# nola6.net
KiCad netlist of a schematic drawn in EAGLE
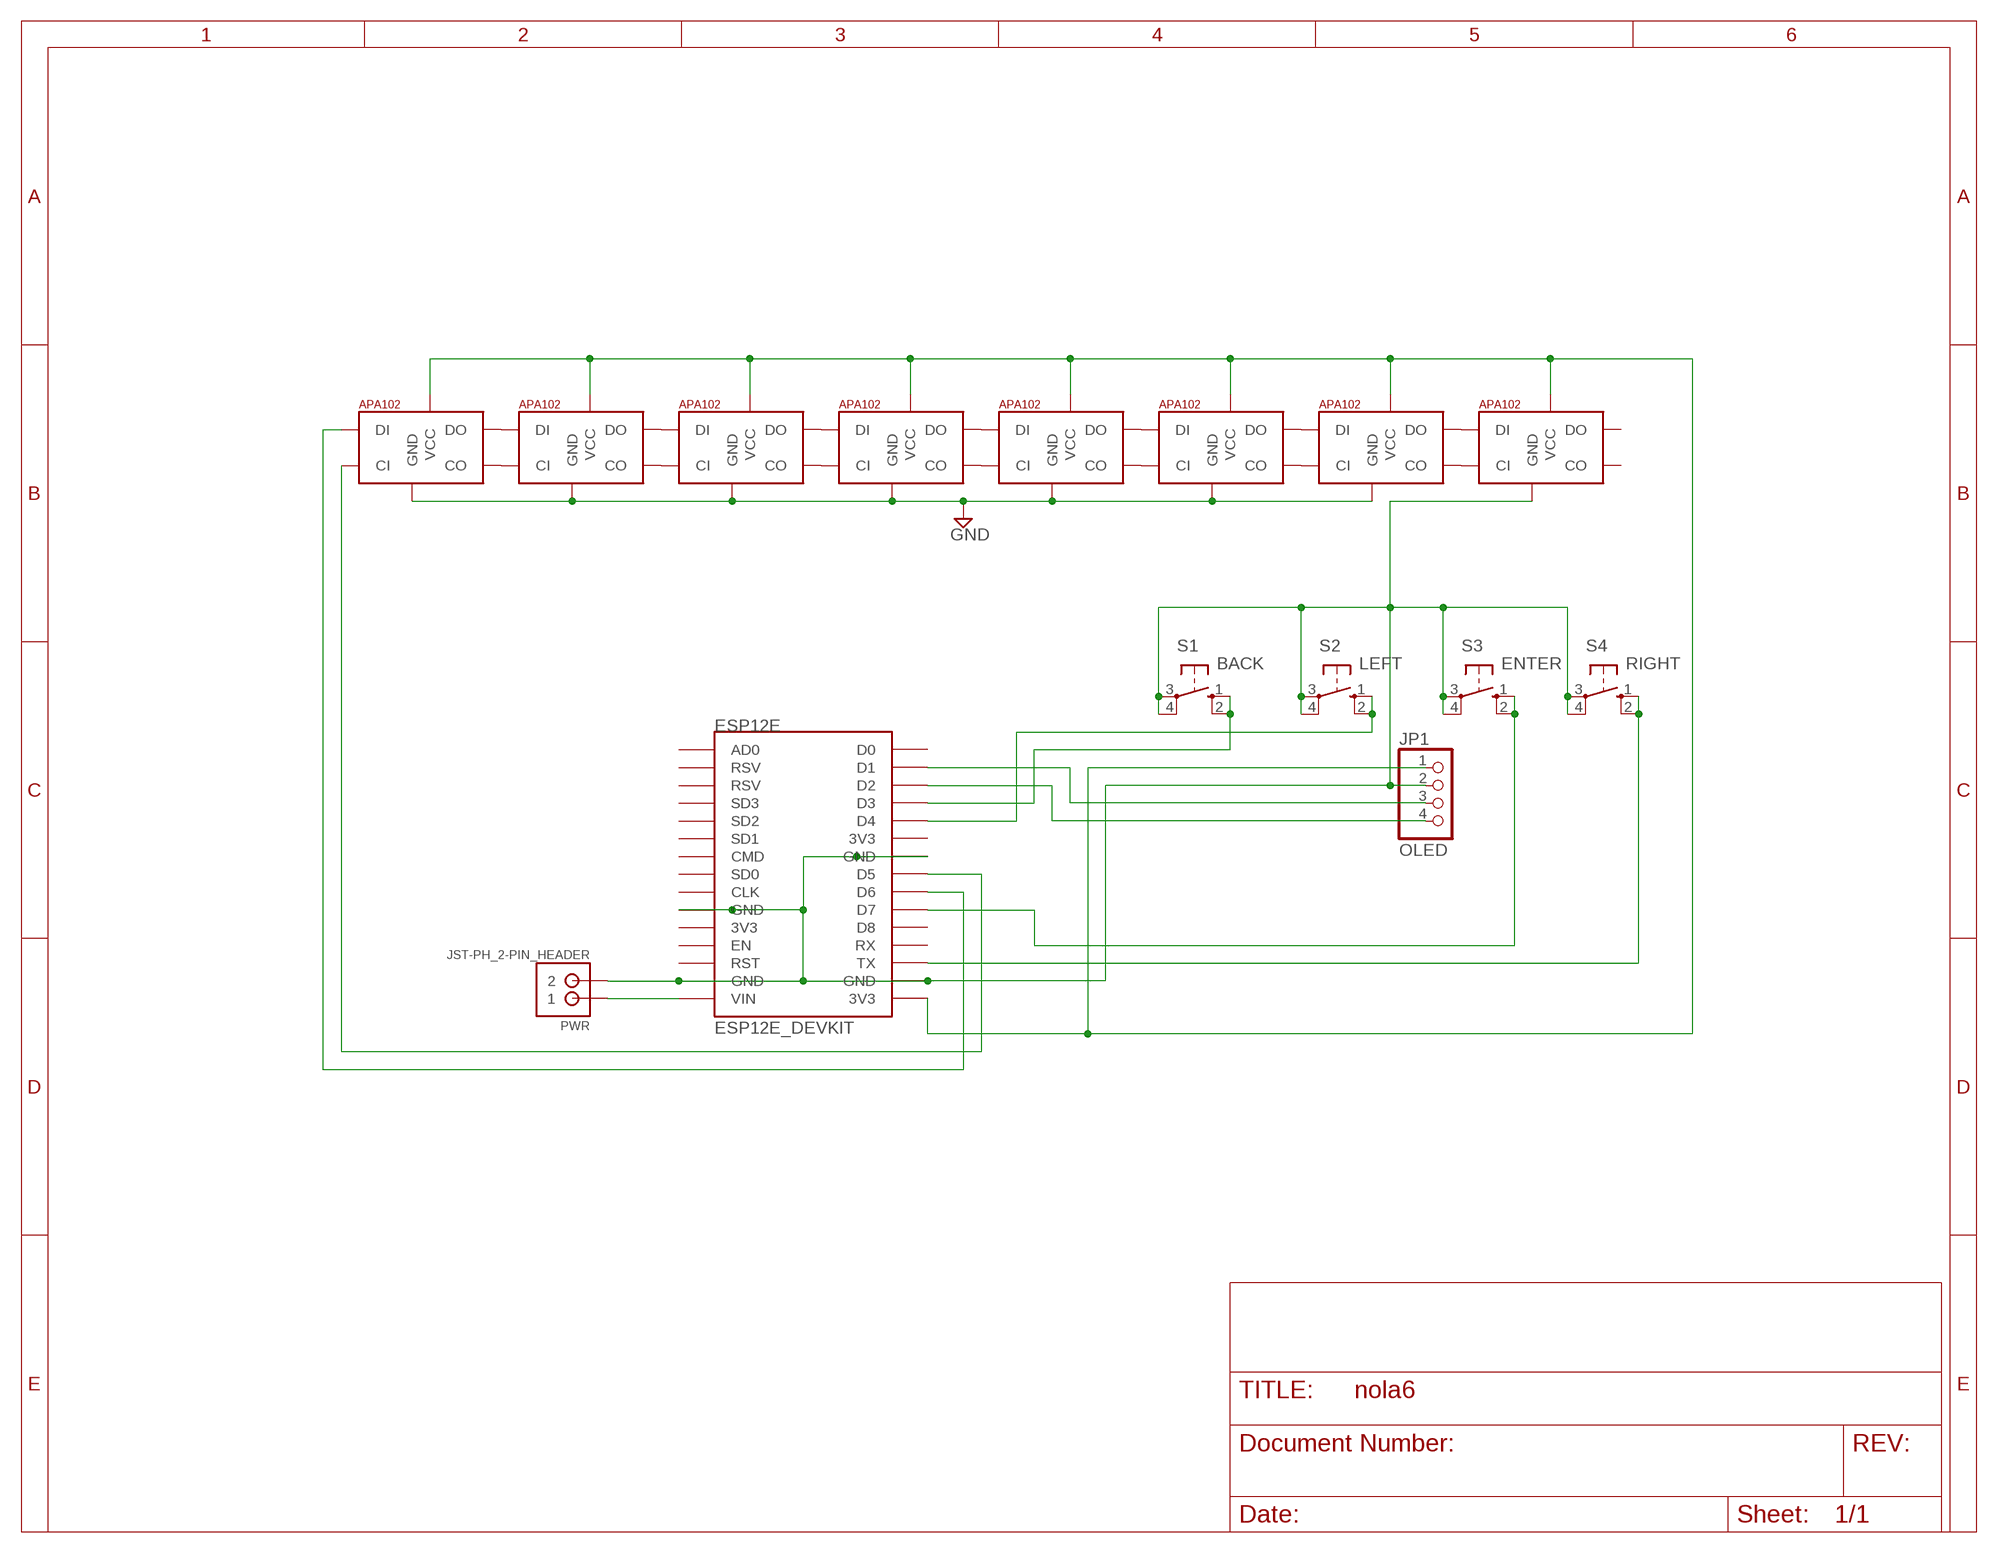
[diagram p0: schematic, sheet 1]

(export (version "E")
  (design (tool "Eeschema 10.0.6"))
  (components
    (comp (ref "ESP12E")
      (value "ESP12E_DEVKIT")
      (footprint "eagle-import:ESP12E_DEVKIT")
      (libsource (lib "eagle-import") (part "ESP12E_DEVKIT"))
    )
    (comp (ref "JP1")
      (value "OLED")
      (footprint "eagle-import:1X04")
      (libsource (lib "eagle-import") (part "PINHD-1X4"))
    )
    (comp (ref "LED1")
      (value "APA1025050")
      (footprint "eagle-import:APA102_5050")
      (libsource (lib "eagle-import") (part "APA1025050"))
    )
    (comp (ref "LED2")
      (value "APA1025050")
      (footprint "eagle-import:APA102_5050")
      (libsource (lib "eagle-import") (part "APA1025050"))
    )
    (comp (ref "LED3")
      (value "APA1025050")
      (footprint "eagle-import:APA102_5050")
      (libsource (lib "eagle-import") (part "APA1025050"))
    )
    (comp (ref "LED4")
      (value "APA1025050")
      (footprint "eagle-import:APA102_5050")
      (libsource (lib "eagle-import") (part "APA1025050"))
    )
    (comp (ref "LED5")
      (value "APA1025050")
      (footprint "eagle-import:APA102_5050")
      (libsource (lib "eagle-import") (part "APA1025050"))
    )
    (comp (ref "LED6")
      (value "APA1025050")
      (footprint "eagle-import:APA102_5050")
      (libsource (lib "eagle-import") (part "APA1025050"))
    )
    (comp (ref "LED7")
      (value "APA1025050")
      (footprint "eagle-import:APA102_5050")
      (libsource (lib "eagle-import") (part "APA1025050"))
    )
    (comp (ref "LED8")
      (value "APA1025050")
      (footprint "eagle-import:APA102_5050")
      (libsource (lib "eagle-import") (part "APA1025050"))
    )
    (comp (ref "PWR")
      (value "JST-PH_2-PIN_HEADER")
      (footprint "eagle-import:JST_B2B-PH_HEADER")
      (libsource (lib "eagle-import") (part "JST-PH_2-PIN_HEADER"))
    )
    (comp (ref "S1")
      (value "BACK")
      (footprint "eagle-import:B3F-10XX")
      (fields (field (name "MPN") "B3F-1000"))
      (libsource (lib "eagle-import") (part "10-XX"))
    )
    (comp (ref "S2")
      (value "LEFT")
      (footprint "eagle-import:B3F-10XX")
      (fields (field (name "MPN") "B3F-1000"))
      (libsource (lib "eagle-import") (part "10-XX"))
    )
    (comp (ref "S3")
      (value "ENTER")
      (footprint "eagle-import:B3F-10XX")
      (fields (field (name "MPN") "B3F-1000"))
      (libsource (lib "eagle-import") (part "10-XX"))
    )
    (comp (ref "S4")
      (value "RIGHT")
      (footprint "eagle-import:B3F-10XX")
      (fields (field (name "MPN") "B3F-1000"))
      (libsource (lib "eagle-import") (part "10-XX"))
    )
  )
  (nets
    (net (code "1") (name "GND") (class "Default")
      (node (ref "ESP12E") (pin "GND@0") (pinfunction "GND_GND@0") (pintype "bidirectional"))
      (node (ref "ESP12E") (pin "GND@1") (pinfunction "GND_GND@1") (pintype "bidirectional"))
      (node (ref "ESP12E") (pin "GND@2") (pinfunction "GND_GND@2") (pintype "bidirectional"))
      (node (ref "ESP12E") (pin "GND@3") (pinfunction "GND_GND@3") (pintype "bidirectional"))
      (node (ref "JP1") (pin "2") (pinfunction "2_2") (pintype "passive"))
      (node (ref "LED1") (pin "6") (pinfunction "GND_6") (pintype "bidirectional"))
      (node (ref "LED2") (pin "6") (pinfunction "GND_6") (pintype "bidirectional"))
      (node (ref "LED3") (pin "6") (pinfunction "GND_6") (pintype "bidirectional"))
      (node (ref "LED4") (pin "6") (pinfunction "GND_6") (pintype "bidirectional"))
      (node (ref "LED5") (pin "6") (pinfunction "GND_6") (pintype "bidirectional"))
      (node (ref "LED6") (pin "6") (pinfunction "GND_6") (pintype "bidirectional"))
      (node (ref "LED7") (pin "6") (pinfunction "GND_6") (pintype "bidirectional"))
      (node (ref "LED8") (pin "6") (pinfunction "GND_6") (pintype "bidirectional"))
      (node (ref "PWR") (pin "P2") (pinfunction "2_P2") (pintype "bidirectional"))
      (node (ref "S1") (pin "3") (pinfunction "P_3") (pintype "passive"))
      (node (ref "S1") (pin "4") (pinfunction "P1_4") (pintype "passive"))
      (node (ref "S2") (pin "3") (pinfunction "P_3") (pintype "passive"))
      (node (ref "S2") (pin "4") (pinfunction "P1_4") (pintype "passive"))
      (node (ref "S3") (pin "3") (pinfunction "P_3") (pintype "passive"))
      (node (ref "S3") (pin "4") (pinfunction "P1_4") (pintype "passive"))
      (node (ref "S4") (pin "3") (pinfunction "P_3") (pintype "passive"))
      (node (ref "S4") (pin "4") (pinfunction "P1_4") (pintype "passive"))
    )
    (net (code "2") (name "Net-(ESP12E-PadD1)") (class "Default")
      (node (ref "ESP12E") (pin "D1") (pinfunction "D1_D1") (pintype "bidirectional"))
      (node (ref "JP1") (pin "3") (pinfunction "3_3") (pintype "passive"))
    )
    (net (code "3") (name "Net-(ESP12E-PadD2)") (class "Default")
      (node (ref "ESP12E") (pin "D2") (pinfunction "D2_D2") (pintype "bidirectional"))
      (node (ref "JP1") (pin "4") (pinfunction "4_4") (pintype "passive"))
    )
    (net (code "4") (name "Net-(LED1-CI)") (class "Default")
      (node (ref "ESP12E") (pin "D5") (pinfunction "D5_D5") (pintype "bidirectional"))
      (node (ref "LED1") (pin "5") (pinfunction "CI_5") (pintype "bidirectional"))
    )
    (net (code "5") (name "Net-(LED1-CO)") (class "Default")
      (node (ref "LED1") (pin "2") (pinfunction "CO_2") (pintype "bidirectional"))
      (node (ref "LED2") (pin "5") (pinfunction "CI_5") (pintype "bidirectional"))
    )
    (net (code "6") (name "Net-(LED1-DI)") (class "Default")
      (node (ref "ESP12E") (pin "D6") (pinfunction "D6_D6") (pintype "bidirectional"))
      (node (ref "LED1") (pin "4") (pinfunction "DI_4") (pintype "bidirectional"))
    )
    (net (code "7") (name "Net-(LED1-DO)") (class "Default")
      (node (ref "LED1") (pin "3") (pinfunction "DO_3") (pintype "bidirectional"))
      (node (ref "LED2") (pin "4") (pinfunction "DI_4") (pintype "bidirectional"))
    )
    (net (code "8") (name "Net-(LED1-VCC)") (class "Default")
      (node (ref "ESP12E") (pin "3V3@2") (pinfunction "3V3_3V3@2") (pintype "bidirectional"))
      (node (ref "JP1") (pin "1") (pinfunction "1_1") (pintype "passive"))
      (node (ref "LED1") (pin "1") (pinfunction "VCC_1") (pintype "bidirectional"))
      (node (ref "LED2") (pin "1") (pinfunction "VCC_1") (pintype "bidirectional"))
      (node (ref "LED3") (pin "1") (pinfunction "VCC_1") (pintype "bidirectional"))
      (node (ref "LED4") (pin "1") (pinfunction "VCC_1") (pintype "bidirectional"))
      (node (ref "LED5") (pin "1") (pinfunction "VCC_1") (pintype "bidirectional"))
      (node (ref "LED6") (pin "1") (pinfunction "VCC_1") (pintype "bidirectional"))
      (node (ref "LED7") (pin "1") (pinfunction "VCC_1") (pintype "bidirectional"))
      (node (ref "LED8") (pin "1") (pinfunction "VCC_1") (pintype "bidirectional"))
    )
    (net (code "9") (name "Net-(LED2-CO)") (class "Default")
      (node (ref "LED2") (pin "2") (pinfunction "CO_2") (pintype "bidirectional"))
      (node (ref "LED3") (pin "5") (pinfunction "CI_5") (pintype "bidirectional"))
    )
    (net (code "10") (name "Net-(LED2-DO)") (class "Default")
      (node (ref "LED2") (pin "3") (pinfunction "DO_3") (pintype "bidirectional"))
      (node (ref "LED3") (pin "4") (pinfunction "DI_4") (pintype "bidirectional"))
    )
    (net (code "11") (name "Net-(LED3-CO)") (class "Default")
      (node (ref "LED3") (pin "2") (pinfunction "CO_2") (pintype "bidirectional"))
      (node (ref "LED4") (pin "5") (pinfunction "CI_5") (pintype "bidirectional"))
    )
    (net (code "12") (name "Net-(LED3-DO)") (class "Default")
      (node (ref "LED3") (pin "3") (pinfunction "DO_3") (pintype "bidirectional"))
      (node (ref "LED4") (pin "4") (pinfunction "DI_4") (pintype "bidirectional"))
    )
    (net (code "13") (name "Net-(LED4-CO)") (class "Default")
      (node (ref "LED4") (pin "2") (pinfunction "CO_2") (pintype "bidirectional"))
      (node (ref "LED5") (pin "5") (pinfunction "CI_5") (pintype "bidirectional"))
    )
    (net (code "14") (name "Net-(LED4-DO)") (class "Default")
      (node (ref "LED4") (pin "3") (pinfunction "DO_3") (pintype "bidirectional"))
      (node (ref "LED5") (pin "4") (pinfunction "DI_4") (pintype "bidirectional"))
    )
    (net (code "15") (name "Net-(LED5-CO)") (class "Default")
      (node (ref "LED5") (pin "2") (pinfunction "CO_2") (pintype "bidirectional"))
      (node (ref "LED6") (pin "5") (pinfunction "CI_5") (pintype "bidirectional"))
    )
    (net (code "16") (name "Net-(LED5-DO)") (class "Default")
      (node (ref "LED5") (pin "3") (pinfunction "DO_3") (pintype "bidirectional"))
      (node (ref "LED6") (pin "4") (pinfunction "DI_4") (pintype "bidirectional"))
    )
    (net (code "17") (name "Net-(LED6-CO)") (class "Default")
      (node (ref "LED6") (pin "2") (pinfunction "CO_2") (pintype "bidirectional"))
      (node (ref "LED7") (pin "5") (pinfunction "CI_5") (pintype "bidirectional"))
    )
    (net (code "18") (name "Net-(LED6-DO)") (class "Default")
      (node (ref "LED6") (pin "3") (pinfunction "DO_3") (pintype "bidirectional"))
      (node (ref "LED7") (pin "4") (pinfunction "DI_4") (pintype "bidirectional"))
    )
    (net (code "19") (name "Net-(LED7-CO)") (class "Default")
      (node (ref "LED7") (pin "2") (pinfunction "CO_2") (pintype "bidirectional"))
      (node (ref "LED8") (pin "5") (pinfunction "CI_5") (pintype "bidirectional"))
    )
    (net (code "20") (name "Net-(LED7-DO)") (class "Default")
      (node (ref "LED7") (pin "3") (pinfunction "DO_3") (pintype "bidirectional"))
      (node (ref "LED8") (pin "4") (pinfunction "DI_4") (pintype "bidirectional"))
    )
    (net (code "21") (name "Net-(PWR-1)") (class "Default")
      (node (ref "ESP12E") (pin "VIN") (pinfunction "VIN_VIN") (pintype "bidirectional"))
      (node (ref "PWR") (pin "P1") (pinfunction "1_P1") (pintype "bidirectional"))
    )
    (net (code "22") (name "Net-(S1-S)") (class "Default")
      (node (ref "ESP12E") (pin "D3") (pinfunction "D3_D3") (pintype "bidirectional"))
      (node (ref "S1") (pin "1") (pinfunction "S_1") (pintype "passive"))
      (node (ref "S1") (pin "2") (pinfunction "S1_2") (pintype "passive"))
    )
    (net (code "23") (name "Net-(S2-S)") (class "Default")
      (node (ref "ESP12E") (pin "D4") (pinfunction "D4_D4") (pintype "bidirectional"))
      (node (ref "S2") (pin "1") (pinfunction "S_1") (pintype "passive"))
      (node (ref "S2") (pin "2") (pinfunction "S1_2") (pintype "passive"))
    )
    (net (code "24") (name "Net-(S3-S)") (class "Default")
      (node (ref "ESP12E") (pin "D7") (pinfunction "D7_D7") (pintype "bidirectional"))
      (node (ref "S3") (pin "1") (pinfunction "S_1") (pintype "passive"))
      (node (ref "S3") (pin "2") (pinfunction "S1_2") (pintype "passive"))
    )
    (net (code "25") (name "Net-(S4-S)") (class "Default")
      (node (ref "ESP12E") (pin "TX") (pinfunction "TX_TX") (pintype "bidirectional"))
      (node (ref "S4") (pin "1") (pinfunction "S_1") (pintype "passive"))
      (node (ref "S4") (pin "2") (pinfunction "S1_2") (pintype "passive"))
    )
    (net (code "26") (name "unconnected-(ESP12E-3V3-Pad3V3@0)") (class "Default")
      (node (ref "ESP12E") (pin "3V3@0") (pinfunction "3V3_3V3@0") (pintype "bidirectional"))
    )
    (net (code "27") (name "unconnected-(ESP12E-3V3-Pad3V3@1)") (class "Default")
      (node (ref "ESP12E") (pin "3V3@1") (pinfunction "3V3_3V3@1") (pintype "bidirectional"))
    )
    (net (code "28") (name "unconnected-(ESP12E-PadAD0)") (class "Default")
      (node (ref "ESP12E") (pin "AD0") (pinfunction "AD0_AD0") (pintype "bidirectional"))
    )
    (net (code "29") (name "unconnected-(ESP12E-PadCLK)") (class "Default")
      (node (ref "ESP12E") (pin "CLK") (pinfunction "CLK_CLK") (pintype "bidirectional"))
    )
    (net (code "30") (name "unconnected-(ESP12E-PadCMD)") (class "Default")
      (node (ref "ESP12E") (pin "CMD") (pinfunction "CMD_CMD") (pintype "bidirectional"))
    )
    (net (code "31") (name "unconnected-(ESP12E-PadD0)") (class "Default")
      (node (ref "ESP12E") (pin "D0") (pinfunction "D0_D0") (pintype "bidirectional"))
    )
    (net (code "32") (name "unconnected-(ESP12E-PadD8)") (class "Default")
      (node (ref "ESP12E") (pin "D8") (pinfunction "D8_D8") (pintype "bidirectional"))
    )
    (net (code "33") (name "unconnected-(ESP12E-PadEN)") (class "Default")
      (node (ref "ESP12E") (pin "EN") (pinfunction "EN_EN") (pintype "bidirectional"))
    )
    (net (code "34") (name "unconnected-(ESP12E-PadRST)") (class "Default")
      (node (ref "ESP12E") (pin "RST") (pinfunction "RST_RST") (pintype "bidirectional"))
    )
    (net (code "35") (name "unconnected-(ESP12E-PadRX)") (class "Default")
      (node (ref "ESP12E") (pin "RX") (pinfunction "RX_RX") (pintype "bidirectional"))
    )
    (net (code "36") (name "unconnected-(ESP12E-PadSD0)") (class "Default")
      (node (ref "ESP12E") (pin "SD0") (pinfunction "SD0_SD0") (pintype "bidirectional"))
    )
    (net (code "37") (name "unconnected-(ESP12E-PadSD1)") (class "Default")
      (node (ref "ESP12E") (pin "SD1") (pinfunction "SD1_SD1") (pintype "bidirectional"))
    )
    (net (code "38") (name "unconnected-(ESP12E-PadSD2)") (class "Default")
      (node (ref "ESP12E") (pin "SD2") (pinfunction "SD2_SD2") (pintype "bidirectional"))
    )
    (net (code "39") (name "unconnected-(ESP12E-PadSD3)") (class "Default")
      (node (ref "ESP12E") (pin "SD3") (pinfunction "SD3_SD3") (pintype "bidirectional"))
    )
    (net (code "40") (name "unconnected-(ESP12E-RSV-PadRSV@0)") (class "Default")
      (node (ref "ESP12E") (pin "RSV@0") (pinfunction "RSV_RSV@0") (pintype "bidirectional"))
    )
    (net (code "41") (name "unconnected-(ESP12E-RSV-PadRSV@1)") (class "Default")
      (node (ref "ESP12E") (pin "RSV@1") (pinfunction "RSV_RSV@1") (pintype "bidirectional"))
    )
    (net (code "42") (name "unconnected-(LED8-CO-Pad2)") (class "Default")
      (node (ref "LED8") (pin "2") (pinfunction "CO_2") (pintype "bidirectional"))
    )
    (net (code "43") (name "unconnected-(LED8-DO-Pad3)") (class "Default")
      (node (ref "LED8") (pin "3") (pinfunction "DO_3") (pintype "bidirectional"))
    )
  )
)
